# ShutdownDPDT-S02-V00-Relay.net
KiCad netlist of a schematic drawn in Altium Designer
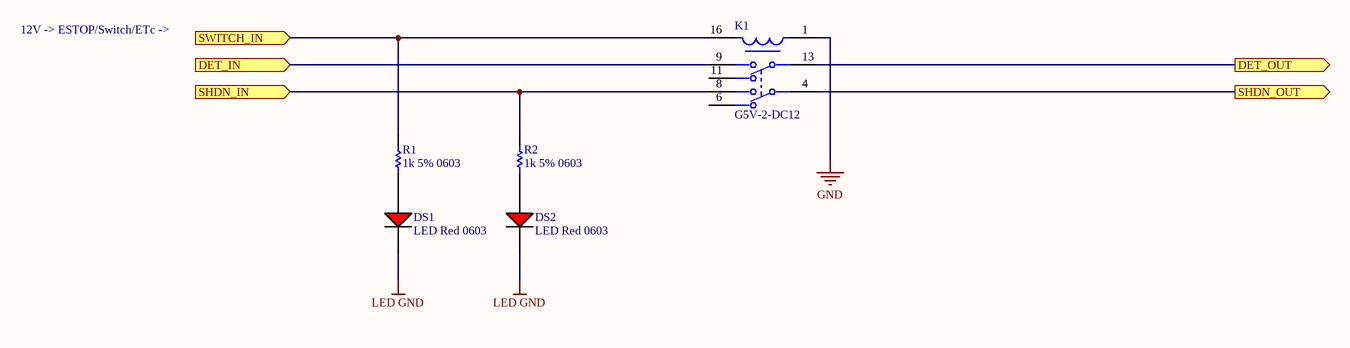
[diagram p0: ShutdownDPDT-S02-V00-Relay.SchDoc]

(export (version "E")
  (design (tool "Eeschema 10.0.6"))
  (components
    (comp (ref "DS1")
      (value "LED Red 0603")
      (footprint "LED RED 0603")
      (libsource (lib "QUTMS_LEDLibrary") (part "LED Red 0603"))
    )
    (comp (ref "DS2")
      (value "LED Red 0603")
      (footprint "LED RED 0603")
      (libsource (lib "QUTMS_LEDLibrary") (part "LED Red 0603"))
    )
    (comp (ref "K1")
      (value "G5V-2-DC12")
      (footprint "FP-G5V-2-DC12-MFG")
      (description "RELAY GEN PURPOSE DPDT 2A 12VDC")
      (libsource (lib "Altium Content Vault") (part "84d1d39ad31b6eb1c8aed030b26f258"))
    )
    (comp (ref "R1")
      (value "1k 5% 0603")
      (footprint "Res_ThinFilm_0603")
      (description "Resistor, SMD, 1k, 0.1W, 5%, 0603")
      (libsource (lib "StandardResistors") (part "1k 5% 0603"))
    )
    (comp (ref "R2")
      (value "1k 5% 0603")
      (footprint "Res_ThinFilm_0603")
      (description "Resistor, SMD, 1k, 0.1W, 5%, 0603")
      (libsource (lib "StandardResistors") (part "1k 5% 0603"))
    )
  )
  (nets
    (net (code "1") (name "/DET_IN") (class "Default")
      (node (ref "K1") (pin "9") (pinfunction "9_9") (pintype "passive"))
    )
    (net (code "2") (name "/DET_OUT") (class "Default")
      (node (ref "K1") (pin "13") (pinfunction "13_13") (pintype "passive"))
    )
    (net (code "3") (name "/SHDN_IN") (class "Default")
      (node (ref "K1") (pin "8") (pinfunction "8_8") (pintype "passive"))
      (node (ref "R2") (pin "2") (pinfunction "2_2") (pintype "passive"))
    )
    (net (code "4") (name "/SHDN_OUT") (class "Default")
      (node (ref "K1") (pin "4") (pinfunction "4_4") (pintype "passive"))
    )
    (net (code "5") (name "/SWITCH_IN") (class "Default")
      (node (ref "K1") (pin "16") (pinfunction "16_16") (pintype "passive"))
      (node (ref "R1") (pin "2") (pinfunction "2_2") (pintype "passive"))
    )
    (net (code "6") (name "GND") (class "Default")
      (node (ref "K1") (pin "1") (pinfunction "1_1") (pintype "passive"))
    )
    (net (code "7") (name "LED GND") (class "Default")
      (node (ref "DS1") (pin "2") (pinfunction "C_2") (pintype "passive"))
      (node (ref "DS2") (pin "2") (pinfunction "C_2") (pintype "passive"))
    )
    (net (code "8") (name "Net-(DS1-A)") (class "Default")
      (node (ref "DS1") (pin "1") (pinfunction "A_1") (pintype "passive"))
      (node (ref "R1") (pin "1") (pinfunction "1_1") (pintype "passive"))
    )
    (net (code "9") (name "Net-(DS2-A)") (class "Default")
      (node (ref "DS2") (pin "1") (pinfunction "A_1") (pintype "passive"))
      (node (ref "R2") (pin "1") (pinfunction "1_1") (pintype "passive"))
    )
    (net (code "10") (name "unconnected-(K1-Pad6)") (class "Default")
      (node (ref "K1") (pin "6") (pinfunction "6_6") (pintype "passive"))
    )
    (net (code "11") (name "unconnected-(K1-Pad11)") (class "Default")
      (node (ref "K1") (pin "11") (pinfunction "11_11") (pintype "passive"))
    )
  )
)
